# fan_thermo_board.net
KiCad netlist of a schematic drawn in EAGLE
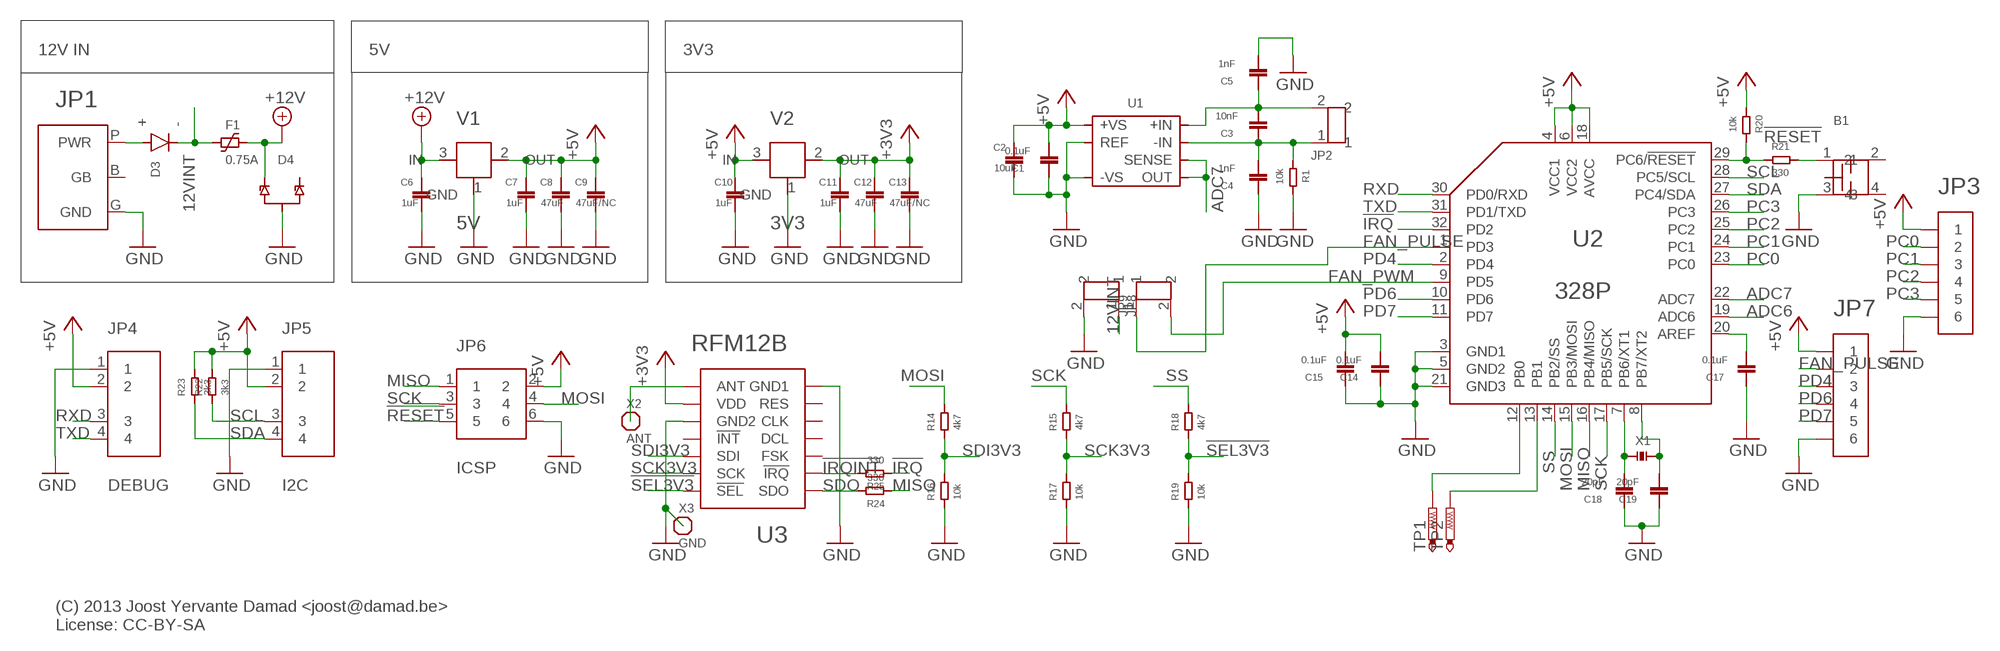
[diagram p0: schematic, sheet 1]

(export (version "E")
  (design (tool "Eeschema 10.0.6"))
  (components
    (comp (ref "B1")
      (value "BUTTON_ALPS_5.2MM_SMD")
      (footprint "eagle-import:BUTTON_ALPS_SMD_5.2MM_SKQG")
      (libsource (lib "eagle-import") (part "BUTTON_ALPS_5.2MM_SMD"))
    )
    (comp (ref "C1")
      (value "0.1uF")
      (footprint "eagle-import:0603@1")
      (libsource (lib "eagle-import") (part "C0603"))
    )
    (comp (ref "C2")
      (value "10uF")
      (footprint "eagle-import:1206")
      (libsource (lib "eagle-import") (part "CAPACITOR1206"))
    )
    (comp (ref "C3")
      (value "10nF")
      (footprint "eagle-import:0603@1")
      (libsource (lib "eagle-import") (part "C0603"))
    )
    (comp (ref "C4")
      (value "1nF")
      (footprint "eagle-import:0603@1")
      (libsource (lib "eagle-import") (part "C0603"))
    )
    (comp (ref "C5")
      (value "1nF")
      (footprint "eagle-import:0603@1")
      (libsource (lib "eagle-import") (part "C0603"))
    )
    (comp (ref "C6")
      (value "1uF")
      (footprint "eagle-import:0603")
      (libsource (lib "eagle-import") (part "CAPACITOR0603"))
    )
    (comp (ref "C7")
      (value "1uF")
      (footprint "eagle-import:0603")
      (libsource (lib "eagle-import") (part "CAPACITOR0603"))
    )
    (comp (ref "C8")
      (value "47uF")
      (footprint "eagle-import:1206")
      (libsource (lib "eagle-import") (part "CAPACITOR1206"))
    )
    (comp (ref "C9")
      (value "47uF/NC")
      (footprint "eagle-import:1206")
      (libsource (lib "eagle-import") (part "CAPACITOR1206"))
    )
    (comp (ref "C10")
      (value "1uF")
      (footprint "eagle-import:0603")
      (libsource (lib "eagle-import") (part "CAPACITOR0603"))
    )
    (comp (ref "C11")
      (value "1uF")
      (footprint "eagle-import:0603")
      (libsource (lib "eagle-import") (part "CAPACITOR0603"))
    )
    (comp (ref "C12")
      (value "47uF")
      (footprint "eagle-import:1206")
      (libsource (lib "eagle-import") (part "CAPACITOR1206"))
    )
    (comp (ref "C13")
      (value "47uF/NC")
      (footprint "eagle-import:1206")
      (libsource (lib "eagle-import") (part "CAPACITOR1206"))
    )
    (comp (ref "C14")
      (value "0.1uF")
      (footprint "eagle-import:0603@1")
      (libsource (lib "eagle-import") (part "C0603"))
    )
    (comp (ref "C15")
      (value "0.1uF")
      (footprint "eagle-import:0603@1")
      (libsource (lib "eagle-import") (part "C0603"))
    )
    (comp (ref "C17")
      (value "0.1uF")
      (footprint "eagle-import:0603@1")
      (libsource (lib "eagle-import") (part "C0603"))
    )
    (comp (ref "C18")
      (value "20pF")
      (footprint "eagle-import:0603@1")
      (libsource (lib "eagle-import") (part "C0603"))
    )
    (comp (ref "C19")
      (value "20pF")
      (footprint "eagle-import:0603@1")
      (libsource (lib "eagle-import") (part "C0603"))
    )
    (comp (ref "D3")
      (value "DIODE")
      (footprint "eagle-import:TAIW_SEM_DIODE")
      (libsource (lib "eagle-import") (part "DIODE"))
    )
    (comp (ref "D4")
      (value "DUAL_TVSSOT-23")
      (footprint "eagle-import:SOT-23")
      (libsource (lib "eagle-import") (part "DUAL_TVSSOT-23"))
    )
    (comp (ref "F1")
      (value "0.75A")
      (footprint "eagle-import:TE_POLYFUSE_1812")
      (libsource (lib "eagle-import") (part "TE_POLYFUSE_1812"))
    )
    (comp (ref "JP1")
      (value "POWER_PLUG_2.1MM")
      (footprint "eagle-import:POWER_PLUG_2.1MM")
      (libsource (lib "eagle-import") (part "POWER_PLUG_2.1MM"))
    )
    (comp (ref "JP2")
      (value "WAGO500-2PIN")
      (footprint "eagle-import:WAGO_500_SCREW_TERMINAL_2_PIN")
      (libsource (lib "eagle-import") (part "WAGO500-2PIN"))
    )
    (comp (ref "JP3")
      (value "PIN1X6")
      (footprint "eagle-import:PIN_1X6")
      (libsource (lib "eagle-import") (part "PIN1X6"))
    )
    (comp (ref "JP4")
      (value "DEBUG")
      (footprint "eagle-import:PIN_1X4")
      (libsource (lib "eagle-import") (part "PIN1X4PTH2.54"))
    )
    (comp (ref "JP5")
      (value "I2C")
      (footprint "eagle-import:JST-S-4B-XH-A")
      (libsource (lib "eagle-import") (part "PIN1X4JSTSIDE"))
    )
    (comp (ref "JP6")
      (value "ICSP")
      (footprint "eagle-import:PIN_2X3_ALT")
      (libsource (lib "eagle-import") (part "PIN2X32X3ALT"))
    )
    (comp (ref "JP7")
      (value "PIN1X6")
      (footprint "eagle-import:PIN_1X6")
      (libsource (lib "eagle-import") (part "PIN1X6"))
    )
    (comp (ref "JP8")
      (value "WAGO500-2PIN")
      (footprint "eagle-import:WAGO_500_SCREW_TERMINAL_2_PIN")
      (libsource (lib "eagle-import") (part "WAGO500-2PIN"))
    )
    (comp (ref "JP9")
      (value "WAGO500-2PIN")
      (footprint "eagle-import:WAGO_500_SCREW_TERMINAL_2_PIN")
      (libsource (lib "eagle-import") (part "WAGO500-2PIN"))
    )
    (comp (ref "R1")
      (value "10k")
      (footprint "eagle-import:0603")
      (libsource (lib "eagle-import") (part "RESISTOR0603"))
    )
    (comp (ref "R14")
      (value "4k7")
      (footprint "eagle-import:0603")
      (libsource (lib "eagle-import") (part "RESISTOR0603"))
    )
    (comp (ref "R15")
      (value "4k7")
      (footprint "eagle-import:0603")
      (libsource (lib "eagle-import") (part "RESISTOR0603"))
    )
    (comp (ref "R16")
      (value "10k")
      (footprint "eagle-import:0603")
      (libsource (lib "eagle-import") (part "RESISTOR0603"))
    )
    (comp (ref "R17")
      (value "10k")
      (footprint "eagle-import:0603")
      (libsource (lib "eagle-import") (part "RESISTOR0603"))
    )
    (comp (ref "R18")
      (value "4k7")
      (footprint "eagle-import:0603")
      (libsource (lib "eagle-import") (part "RESISTOR0603"))
    )
    (comp (ref "R19")
      (value "10k")
      (footprint "eagle-import:0603")
      (libsource (lib "eagle-import") (part "RESISTOR0603"))
    )
    (comp (ref "R20")
      (value "10k")
      (footprint "eagle-import:0603")
      (libsource (lib "eagle-import") (part "RESISTOR0603"))
    )
    (comp (ref "R21")
      (value "330")
      (footprint "eagle-import:0603")
      (libsource (lib "eagle-import") (part "RESISTOR0603"))
    )
    (comp (ref "R22")
      (value "3k3")
      (footprint "eagle-import:0603")
      (libsource (lib "eagle-import") (part "RESISTOR0603"))
    )
    (comp (ref "R23")
      (value "3k3")
      (footprint "eagle-import:0603")
      (libsource (lib "eagle-import") (part "RESISTOR0603"))
    )
    (comp (ref "R24")
      (value "330")
      (footprint "eagle-import:0603")
      (libsource (lib "eagle-import") (part "RESISTOR0603"))
    )
    (comp (ref "R25")
      (value "330")
      (footprint "eagle-import:0603")
      (libsource (lib "eagle-import") (part "RESISTOR0603"))
    )
    (comp (ref "TP1")
      (value "PTR1B1,27")
      (footprint "eagle-import:B1,27")
      (libsource (lib "eagle-import") (part "PTR1B1,27"))
    )
    (comp (ref "TP2")
      (value "PTR1B1,27")
      (footprint "eagle-import:B1,27")
      (libsource (lib "eagle-import") (part "PTR1B1,27"))
    )
    (comp (ref "U1")
      (value "AD8495")
      (footprint "eagle-import:JEDEC_MO-187-AA")
      (libsource (lib "eagle-import") (part "AD8495"))
    )
    (comp (ref "U2")
      (value "328P")
      (footprint "eagle-import:TQFP32")
      (libsource (lib "eagle-import") (part "ATMEGA328PTQFP32"))
    )
    (comp (ref "U3")
      (value "RFM12B")
      (footprint "eagle-import:RFM12B")
      (libsource (lib "eagle-import") (part "RFM12B"))
    )
    (comp (ref "V1")
      (value "5V")
      (footprint "eagle-import:SOT-23A")
      (libsource (lib "eagle-import") (part "VREG_MCP1703"))
    )
    (comp (ref "V2")
      (value "3V3")
      (footprint "eagle-import:SOT-23A")
      (libsource (lib "eagle-import") (part "VREG_MCP1703"))
    )
    (comp (ref "X1")
      (value "CRYSTAL")
      (footprint "eagle-import:CRYSTAL_2-PAD_5X3.2MM")
      (libsource (lib "eagle-import") (part "CRYSTAL"))
    )
    (comp (ref "X2")
      (value "ANT")
      (footprint "eagle-import:PIN_1X1")
      (libsource (lib "eagle-import") (part "PIN1X1"))
    )
    (comp (ref "X3")
      (value "GND")
      (footprint "eagle-import:PIN_1X1")
      (libsource (lib "eagle-import") (part "PIN1X1"))
    )
  )
  (nets
    (net (code "1") (name "+3V3") (class "Default")
      (node (ref "C11") (pin "2") (pinfunction "1_2") (pintype "passive"))
      (node (ref "C12") (pin "1") (pinfunction "1_1") (pintype "passive"))
      (node (ref "C13") (pin "1") (pinfunction "1_1") (pintype "passive"))
      (node (ref "U3") (pin "VDD") (pinfunction "VDD_VDD") (pintype "bidirectional"))
      (node (ref "V2") (pin "2") (pinfunction "OUT_2") (pintype "bidirectional"))
    )
    (net (code "2") (name "+5V") (class "Default")
      (node (ref "C1") (pin "1") (pinfunction "2_1") (pintype "passive"))
      (node (ref "C10") (pin "2") (pinfunction "1_2") (pintype "passive"))
      (node (ref "C14") (pin "1") (pinfunction "2_1") (pintype "passive"))
      (node (ref "C15") (pin "1") (pinfunction "2_1") (pintype "passive"))
      (node (ref "C2") (pin "1") (pinfunction "1_1") (pintype "passive"))
      (node (ref "C7") (pin "2") (pinfunction "1_2") (pintype "passive"))
      (node (ref "C8") (pin "1") (pinfunction "1_1") (pintype "passive"))
      (node (ref "C9") (pin "1") (pinfunction "1_1") (pintype "passive"))
      (node (ref "JP3") (pin "1") (pinfunction "1_1") (pintype "bidirectional"))
      (node (ref "JP4") (pin "2") (pinfunction "2_2") (pintype "bidirectional"))
      (node (ref "JP5") (pin "2") (pinfunction "2_2") (pintype "bidirectional"))
      (node (ref "JP6") (pin "2") (pinfunction "2_2") (pintype "bidirectional"))
      (node (ref "JP7") (pin "1") (pinfunction "1_1") (pintype "bidirectional"))
      (node (ref "R20") (pin "1") (pinfunction "1_1") (pintype "passive"))
      (node (ref "R22") (pin "2") (pinfunction "2_2") (pintype "passive"))
      (node (ref "R23") (pin "2") (pinfunction "2_2") (pintype "passive"))
      (node (ref "U1") (pin "7") (pinfunction "+VS_7") (pintype "bidirectional"))
      (node (ref "U2") (pin "18") (pinfunction "AVCC_18") (pintype "bidirectional"))
      (node (ref "U2") (pin "4") (pinfunction "VCC1_4") (pintype "bidirectional"))
      (node (ref "U2") (pin "6") (pinfunction "VCC2_6") (pintype "bidirectional"))
      (node (ref "V1") (pin "2") (pinfunction "OUT_2") (pintype "bidirectional"))
      (node (ref "V2") (pin "3") (pinfunction "IN_3") (pintype "bidirectional"))
    )
    (net (code "3") (name "+12V") (class "Default")
      (node (ref "C6") (pin "2") (pinfunction "1_2") (pintype "passive"))
      (node (ref "D4") (pin "1") (pinfunction "P1_1") (pintype "bidirectional"))
      (node (ref "F1") (pin "2") (pinfunction "P$2_2") (pintype "bidirectional"))
      (node (ref "V1") (pin "3") (pinfunction "IN_3") (pintype "bidirectional"))
    )
    (net (code "4") (name "/12VINT") (class "Default")
      (node (ref "D3") (pin "-") (pinfunction "-_-") (pintype "bidirectional"))
      (node (ref "F1") (pin "1") (pinfunction "P$1_1") (pintype "bidirectional"))
      (node (ref "JP8") (pin "1") (pinfunction "1_1") (pintype "bidirectional"))
    )
    (net (code "5") (name "/ADC6") (class "Default")
      (node (ref "U2") (pin "19") (pinfunction "ADC6_19") (pintype "bidirectional"))
    )
    (net (code "6") (name "/ADC7") (class "Default")
      (node (ref "U1") (pin "5") (pinfunction "SENSE_5") (pintype "bidirectional"))
      (node (ref "U1") (pin "6") (pinfunction "OUT_6") (pintype "bidirectional"))
      (node (ref "U2") (pin "22") (pinfunction "ADC7_22") (pintype "bidirectional"))
    )
    (net (code "7") (name "/FAN_PULSE") (class "Default")
      (node (ref "JP7") (pin "2") (pinfunction "2_2") (pintype "bidirectional"))
      (node (ref "JP9") (pin "1") (pinfunction "1_1") (pintype "bidirectional"))
      (node (ref "U2") (pin "1") (pinfunction "PD3_1") (pintype "bidirectional"))
    )
    (net (code "8") (name "/FAN_PWM") (class "Default")
      (node (ref "JP9") (pin "2") (pinfunction "2_2") (pintype "bidirectional"))
      (node (ref "U2") (pin "9") (pinfunction "PD5_9") (pintype "bidirectional"))
    )
    (net (code "9") (name "/MISO") (class "Default")
      (node (ref "JP6") (pin "1") (pinfunction "1_1") (pintype "bidirectional"))
      (node (ref "R24") (pin "1") (pinfunction "1_1") (pintype "passive"))
      (node (ref "U2") (pin "16") (pinfunction "PB4/MISO_16") (pintype "bidirectional"))
    )
    (net (code "10") (name "/MOSI") (class "Default")
      (node (ref "JP6") (pin "4") (pinfunction "4_4") (pintype "bidirectional"))
      (node (ref "R14") (pin "2") (pinfunction "2_2") (pintype "passive"))
      (node (ref "U2") (pin "15") (pinfunction "PB3/MOSI_15") (pintype "bidirectional"))
    )
    (net (code "11") (name "/PC0") (class "Default")
      (node (ref "JP3") (pin "2") (pinfunction "2_2") (pintype "bidirectional"))
      (node (ref "U2") (pin "23") (pinfunction "PC0_23") (pintype "bidirectional"))
    )
    (net (code "12") (name "/PC1") (class "Default")
      (node (ref "JP3") (pin "3") (pinfunction "3_3") (pintype "bidirectional"))
      (node (ref "U2") (pin "24") (pinfunction "PC1_24") (pintype "bidirectional"))
    )
    (net (code "13") (name "/PC2") (class "Default")
      (node (ref "JP3") (pin "4") (pinfunction "4_4") (pintype "bidirectional"))
      (node (ref "U2") (pin "25") (pinfunction "PC2_25") (pintype "bidirectional"))
    )
    (net (code "14") (name "/PC3") (class "Default")
      (node (ref "JP3") (pin "5") (pinfunction "5_5") (pintype "bidirectional"))
      (node (ref "U2") (pin "26") (pinfunction "PC3_26") (pintype "bidirectional"))
    )
    (net (code "15") (name "/PD4") (class "Default")
      (node (ref "JP7") (pin "3") (pinfunction "3_3") (pintype "bidirectional"))
      (node (ref "U2") (pin "2") (pinfunction "PD4_2") (pintype "bidirectional"))
    )
    (net (code "16") (name "/PD6") (class "Default")
      (node (ref "JP7") (pin "4") (pinfunction "4_4") (pintype "bidirectional"))
      (node (ref "U2") (pin "10") (pinfunction "PD6_10") (pintype "bidirectional"))
    )
    (net (code "17") (name "/PD7") (class "Default")
      (node (ref "JP7") (pin "5") (pinfunction "5_5") (pintype "bidirectional"))
      (node (ref "U2") (pin "11") (pinfunction "PD7_11") (pintype "bidirectional"))
    )
    (net (code "18") (name "/RXD") (class "Default")
      (node (ref "JP4") (pin "3") (pinfunction "3_3") (pintype "bidirectional"))
      (node (ref "U2") (pin "30") (pinfunction "PD0/RXD_30") (pintype "bidirectional"))
    )
    (net (code "19") (name "/SCK") (class "Default")
      (node (ref "JP6") (pin "3") (pinfunction "3_3") (pintype "bidirectional"))
      (node (ref "R15") (pin "2") (pinfunction "2_2") (pintype "passive"))
      (node (ref "U2") (pin "17") (pinfunction "PB5/SCK_17") (pintype "bidirectional"))
    )
    (net (code "20") (name "/SCK3V3") (class "Default")
      (node (ref "R15") (pin "1") (pinfunction "1_1") (pintype "passive"))
      (node (ref "R17") (pin "2") (pinfunction "2_2") (pintype "passive"))
      (node (ref "U3") (pin "SCK") (pinfunction "SCK_SCK") (pintype "bidirectional"))
    )
    (net (code "21") (name "/SCL") (class "Default")
      (node (ref "JP5") (pin "3") (pinfunction "3_3") (pintype "bidirectional"))
      (node (ref "R22") (pin "1") (pinfunction "1_1") (pintype "passive"))
      (node (ref "U2") (pin "28") (pinfunction "PC5/SCL_28") (pintype "bidirectional"))
    )
    (net (code "22") (name "/SDA") (class "Default")
      (node (ref "JP5") (pin "4") (pinfunction "4_4") (pintype "bidirectional"))
      (node (ref "R23") (pin "1") (pinfunction "1_1") (pintype "passive"))
      (node (ref "U2") (pin "27") (pinfunction "PC4/SDA_27") (pintype "bidirectional"))
    )
    (net (code "23") (name "/SDI3V3") (class "Default")
      (node (ref "R14") (pin "1") (pinfunction "1_1") (pintype "passive"))
      (node (ref "R16") (pin "2") (pinfunction "2_2") (pintype "passive"))
      (node (ref "U3") (pin "SDI") (pinfunction "SDI_SDI") (pintype "bidirectional"))
    )
    (net (code "24") (name "/SDO") (class "Default")
      (node (ref "R24") (pin "2") (pinfunction "2_2") (pintype "passive"))
      (node (ref "U3") (pin "SDO") (pinfunction "SDO_SDO") (pintype "bidirectional"))
    )
    (net (code "25") (name "/SS") (class "Default")
      (node (ref "R18") (pin "2") (pinfunction "2_2") (pintype "passive"))
      (node (ref "U2") (pin "14") (pinfunction "PB2/SS_14") (pintype "bidirectional"))
    )
    (net (code "26") (name "/TXD") (class "Default")
      (node (ref "JP4") (pin "4") (pinfunction "4_4") (pintype "bidirectional"))
      (node (ref "U2") (pin "31") (pinfunction "PD1/TXD_31") (pintype "bidirectional"))
    )
    (net (code "27") (name "/~{IRQINT}") (class "Default")
      (node (ref "R25") (pin "2") (pinfunction "2_2") (pintype "passive"))
      (node (ref "U3") (pin "NIRQ") (pinfunction "~{IRQ}_NIRQ") (pintype "bidirectional"))
    )
    (net (code "28") (name "/~{IRQ}") (class "Default")
      (node (ref "R25") (pin "1") (pinfunction "1_1") (pintype "passive"))
      (node (ref "U2") (pin "32") (pinfunction "PD2_32") (pintype "bidirectional"))
    )
    (net (code "29") (name "/~{RESET}") (class "Default")
      (node (ref "JP6") (pin "5") (pinfunction "5_5") (pintype "bidirectional"))
      (node (ref "R20") (pin "2") (pinfunction "2_2") (pintype "passive"))
      (node (ref "R21") (pin "1") (pinfunction "1_1") (pintype "passive"))
      (node (ref "U2") (pin "29") (pinfunction "PC6/~{RESET}_29") (pintype "bidirectional"))
    )
    (net (code "30") (name "/~{SEL3V3}") (class "Default")
      (node (ref "R18") (pin "1") (pinfunction "1_1") (pintype "passive"))
      (node (ref "R19") (pin "2") (pinfunction "2_2") (pintype "passive"))
      (node (ref "U3") (pin "NSEL") (pinfunction "~{SEL}_NSEL") (pintype "bidirectional"))
    )
    (net (code "31") (name "GND") (class "Default")
      (node (ref "B1") (pin "3") (pinfunction "3_3") (pintype "bidirectional"))
      (node (ref "C1") (pin "2") (pinfunction "1_2") (pintype "passive"))
      (node (ref "C10") (pin "1") (pinfunction "2_1") (pintype "passive"))
      (node (ref "C11") (pin "1") (pinfunction "2_1") (pintype "passive"))
      (node (ref "C12") (pin "2") (pinfunction "2_2") (pintype "passive"))
      (node (ref "C13") (pin "2") (pinfunction "2_2") (pintype "passive"))
      (node (ref "C14") (pin "2") (pinfunction "1_2") (pintype "passive"))
      (node (ref "C15") (pin "2") (pinfunction "1_2") (pintype "passive"))
      (node (ref "C17") (pin "2") (pinfunction "1_2") (pintype "passive"))
      (node (ref "C18") (pin "2") (pinfunction "1_2") (pintype "passive"))
      (node (ref "C19") (pin "2") (pinfunction "1_2") (pintype "passive"))
      (node (ref "C2") (pin "2") (pinfunction "2_2") (pintype "passive"))
      (node (ref "C4") (pin "2") (pinfunction "1_2") (pintype "passive"))
      (node (ref "C5") (pin "1") (pinfunction "2_1") (pintype "passive"))
      (node (ref "C6") (pin "1") (pinfunction "2_1") (pintype "passive"))
      (node (ref "C7") (pin "1") (pinfunction "2_1") (pintype "passive"))
      (node (ref "C8") (pin "2") (pinfunction "2_2") (pintype "passive"))
      (node (ref "C9") (pin "2") (pinfunction "2_2") (pintype "passive"))
      (node (ref "D4") (pin "3") (pinfunction "G1_3") (pintype "bidirectional"))
      (node (ref "JP1") (pin "G") (pinfunction "GND_G") (pintype "bidirectional"))
      (node (ref "JP3") (pin "6") (pinfunction "6_6") (pintype "bidirectional"))
      (node (ref "JP4") (pin "1") (pinfunction "1_1") (pintype "bidirectional"))
      (node (ref "JP5") (pin "1") (pinfunction "1_1") (pintype "bidirectional"))
      (node (ref "JP6") (pin "6") (pinfunction "6_6") (pintype "bidirectional"))
      (node (ref "JP7") (pin "6") (pinfunction "6_6") (pintype "bidirectional"))
      (node (ref "JP8") (pin "2") (pinfunction "2_2") (pintype "bidirectional"))
      (node (ref "R1") (pin "2") (pinfunction "2_2") (pintype "passive"))
      (node (ref "R16") (pin "1") (pinfunction "1_1") (pintype "passive"))
      (node (ref "R17") (pin "1") (pinfunction "1_1") (pintype "passive"))
      (node (ref "R19") (pin "1") (pinfunction "1_1") (pintype "passive"))
      (node (ref "U1") (pin "2") (pinfunction "REF_2") (pintype "bidirectional"))
      (node (ref "U1") (pin "3") (pinfunction "-VS_3") (pintype "bidirectional"))
      (node (ref "U2") (pin "21") (pinfunction "GND3_21") (pintype "bidirectional"))
      (node (ref "U2") (pin "3") (pinfunction "GND1_3") (pintype "bidirectional"))
      (node (ref "U2") (pin "5") (pinfunction "GND2_5") (pintype "bidirectional"))
      (node (ref "U3") (pin "GND@1") (pinfunction "GND1_GND@1") (pintype "bidirectional"))
      (node (ref "U3") (pin "GND@2") (pinfunction "GND2_GND@2") (pintype "bidirectional"))
      (node (ref "V1") (pin "1") (pinfunction "GND_1") (pintype "bidirectional"))
      (node (ref "V2") (pin "1") (pinfunction "GND_1") (pintype "bidirectional"))
      (node (ref "X3") (pin "1") (pinfunction "P$1_1") (pintype "bidirectional"))
    )
    (net (code "32") (name "Net-(B1-Pad1)") (class "Default")
      (node (ref "B1") (pin "1") (pinfunction "1_1") (pintype "bidirectional"))
      (node (ref "R21") (pin "2") (pinfunction "2_2") (pintype "passive"))
    )
    (net (code "33") (name "Net-(C3-1)") (class "Default")
      (node (ref "C3") (pin "2") (pinfunction "1_2") (pintype "passive"))
      (node (ref "C4") (pin "1") (pinfunction "2_1") (pintype "passive"))
      (node (ref "JP2") (pin "1") (pinfunction "1_1") (pintype "bidirectional"))
      (node (ref "R1") (pin "1") (pinfunction "1_1") (pintype "passive"))
      (node (ref "U1") (pin "1") (pinfunction "-IN_1") (pintype "bidirectional"))
    )
    (net (code "34") (name "Net-(C3-2)") (class "Default")
      (node (ref "C3") (pin "1") (pinfunction "2_1") (pintype "passive"))
      (node (ref "C5") (pin "2") (pinfunction "1_2") (pintype "passive"))
      (node (ref "JP2") (pin "2") (pinfunction "2_2") (pintype "bidirectional"))
      (node (ref "U1") (pin "8") (pinfunction "+IN_8") (pintype "bidirectional"))
    )
    (net (code "35") (name "Net-(C17-2)") (class "Default")
      (node (ref "C17") (pin "1") (pinfunction "2_1") (pintype "passive"))
      (node (ref "U2") (pin "20") (pinfunction "AREF_20") (pintype "bidirectional"))
    )
    (net (code "36") (name "Net-(C18-2)") (class "Default")
      (node (ref "C18") (pin "1") (pinfunction "2_1") (pintype "passive"))
      (node (ref "U2") (pin "7") (pinfunction "PB6/XT1_7") (pintype "bidirectional"))
      (node (ref "X1") (pin "1") (pinfunction "P$1_1") (pintype "bidirectional"))
    )
    (net (code "37") (name "Net-(C19-2)") (class "Default")
      (node (ref "C19") (pin "1") (pinfunction "2_1") (pintype "passive"))
      (node (ref "U2") (pin "8") (pinfunction "PB7/XT2_8") (pintype "bidirectional"))
      (node (ref "X1") (pin "2") (pinfunction "P$2_2") (pintype "bidirectional"))
    )
    (net (code "38") (name "Net-(JP1-PWR)") (class "Default")
      (node (ref "D3") (pin "+") (pinfunction "+_+") (pintype "bidirectional"))
      (node (ref "JP1") (pin "P") (pinfunction "PWR_P") (pintype "bidirectional"))
    )
    (net (code "39") (name "Net-(U2-PB0)") (class "Default")
      (node (ref "TP1") (pin "TP") (pinfunction "TP_TP") (pintype "input"))
      (node (ref "U2") (pin "12") (pinfunction "PB0_12") (pintype "bidirectional"))
    )
    (net (code "40") (name "Net-(U2-PB1)") (class "Default")
      (node (ref "TP2") (pin "TP") (pinfunction "TP_TP") (pintype "input"))
      (node (ref "U2") (pin "13") (pinfunction "PB1_13") (pintype "bidirectional"))
    )
    (net (code "41") (name "Net-(X2-P$1)") (class "Default")
      (node (ref "U3") (pin "ANT") (pinfunction "ANT_ANT") (pintype "bidirectional"))
      (node (ref "X2") (pin "1") (pinfunction "P$1_1") (pintype "bidirectional"))
    )
    (net (code "42") (name "unconnected-(B1-Pad2)") (class "Default")
      (node (ref "B1") (pin "2") (pinfunction "2_2") (pintype "bidirectional"))
    )
    (net (code "43") (name "unconnected-(B1-Pad4)") (class "Default")
      (node (ref "B1") (pin "4") (pinfunction "4_4") (pintype "bidirectional"))
    )
    (net (code "44") (name "unconnected-(D4-P2-Pad2)") (class "Default")
      (node (ref "D4") (pin "2") (pinfunction "P2_2") (pintype "bidirectional"))
    )
    (net (code "45") (name "unconnected-(JP1-GB-PadB)") (class "Default")
      (node (ref "JP1") (pin "B") (pinfunction "GB_B") (pintype "bidirectional"))
    )
    (net (code "46") (name "unconnected-(U3-PadCLK)") (class "Default")
      (node (ref "U3") (pin "CLK") (pinfunction "CLK_CLK") (pintype "bidirectional"))
    )
    (net (code "47") (name "unconnected-(U3-PadDCL)") (class "Default")
      (node (ref "U3") (pin "DCL") (pinfunction "DCL_DCL") (pintype "bidirectional"))
    )
    (net (code "48") (name "unconnected-(U3-PadFSK)") (class "Default")
      (node (ref "U3") (pin "FSK") (pinfunction "FSK_FSK") (pintype "bidirectional"))
    )
    (net (code "49") (name "unconnected-(U3-PadRES)") (class "Default")
      (node (ref "U3") (pin "RES") (pinfunction "RES_RES") (pintype "bidirectional"))
    )
    (net (code "50") (name "unconnected-(U3-~{INT}-PadNINT)") (class "Default")
      (node (ref "U3") (pin "NINT") (pinfunction "~{INT}_NINT") (pintype "bidirectional"))
    )
  )
)
